# INTERFACE.net
KiCad netlist of a schematic drawn in Altium Designer
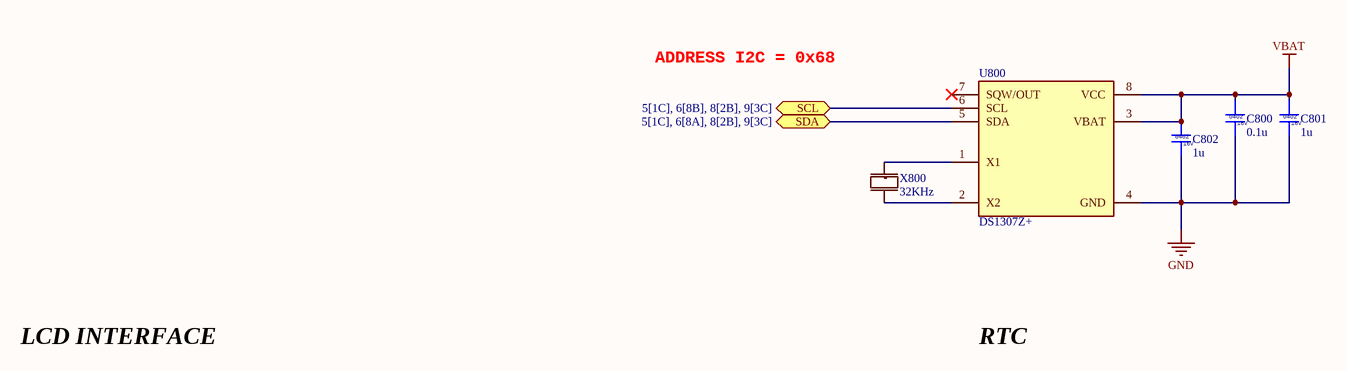
[diagram p0: INTERFACE.SchDoc]

(export (version "E")
  (design (tool "Eeschema 10.0.6"))
  (components
    (comp (ref "C800")
      (value "0.1u")
      (footprint "CAP0402")
      (fields
        (field (name "MANUFACTURER") "Murata")
        (field (name "MANUFACTURER PART NUMBER") "GRM155R71C104KA88J")
      )
      (libsource (lib "Hw_Lib") (part "C_0402_0.1u"))
    )
    (comp (ref "C801")
      (value "1u")
      (footprint "CAP0402")
      (fields
        (field (name "MANUFACTURER") "Taiyo Yuden")
        (field (name "MANUFACTURER PART NUMBER") "EMK105BJ105KV-F")
      )
      (libsource (lib "Hw_Lib") (part "C_0402_1u"))
    )
    (comp (ref "C802")
      (value "1u")
      (footprint "CAP0402")
      (fields
        (field (name "MANUFACTURER") "Taiyo Yuden")
        (field (name "MANUFACTURER PART NUMBER") "EMK105BJ105KV-F")
      )
      (libsource (lib "Hw_Lib") (part "C_0402_1u"))
    )
    (comp (ref "U800")
      (value "DS1307Z+")
      (footprint "DS1307+")
      (description "Real Time Clock, Volatile, 1 Timer(s), CMOS, PDSO8")
      (fields (field (name "MANUFACTURER") "Maxim"))
      (libsource (lib "Hw_Lib") (part "DS1307Z+"))
    )
    (comp (ref "X800")
      (value "32KHz")
      (footprint "32Khz")
      (description "CRYSTAL 32.7680KHZ 12.5PF SMD")
      (fields
        (field (name "MANUFACTURER") "Micro Crystal")
        (field (name "MANUFACTURER PART NUMBER") "CM8V-T1A-32.768KHZ-12.5PF-20PPM-TA-QA")
      )
      (libsource (lib "Hw_Lib") (part "CM8V-T1A-32.768KHZ-12.5PF-20PPM-TA-QA"))
    )
  )
  (nets
    (net (code "1") (name "/SCL") (class "Default")
      (node (ref "U800") (pin "6") (pinfunction "SCL_6") (pintype "open_collector"))
    )
    (net (code "2") (name "/SDA") (class "Default")
      (node (ref "U800") (pin "5") (pinfunction "SDA_5") (pintype "open_collector"))
    )
    (net (code "3") (name "GND") (class "Default")
      (node (ref "C800") (pin "2") (pinfunction "2_2") (pintype "passive"))
      (node (ref "C801") (pin "2") (pinfunction "2_2") (pintype "passive"))
      (node (ref "C802") (pin "2") (pinfunction "2_2") (pintype "passive"))
      (node (ref "U800") (pin "4") (pinfunction "GND_4") (pintype "open_collector"))
    )
    (net (code "4") (name "Net-(U800-X1)") (class "Default")
      (node (ref "U800") (pin "1") (pinfunction "X1_1") (pintype "open_collector"))
      (node (ref "X800") (pin "1") (pinfunction "1_1") (pintype "passive"))
    )
    (net (code "5") (name "Net-(U800-X2)") (class "Default")
      (node (ref "U800") (pin "2") (pinfunction "X2_2") (pintype "open_collector"))
      (node (ref "X800") (pin "2") (pinfunction "2_2") (pintype "passive"))
    )
    (net (code "6") (name "VBAT") (class "Default")
      (node (ref "C800") (pin "1") (pinfunction "1_1") (pintype "passive"))
      (node (ref "C801") (pin "1") (pinfunction "1_1") (pintype "passive"))
      (node (ref "C802") (pin "1") (pinfunction "1_1") (pintype "passive"))
      (node (ref "U800") (pin "3") (pinfunction "VBAT_3") (pintype "open_collector"))
      (node (ref "U800") (pin "8") (pinfunction "VCC_8") (pintype "open_collector"))
    )
    (net (code "7") (name "unconnected-(U800-SQW{slash}OUT-Pad7)") (class "Default")
      (node (ref "U800") (pin "7") (pinfunction "SQW/OUT_7") (pintype "open_collector+no_connect"))
    )
  )
)
